# FPGA.net
KiCad netlist of a schematic drawn in Altium Designer
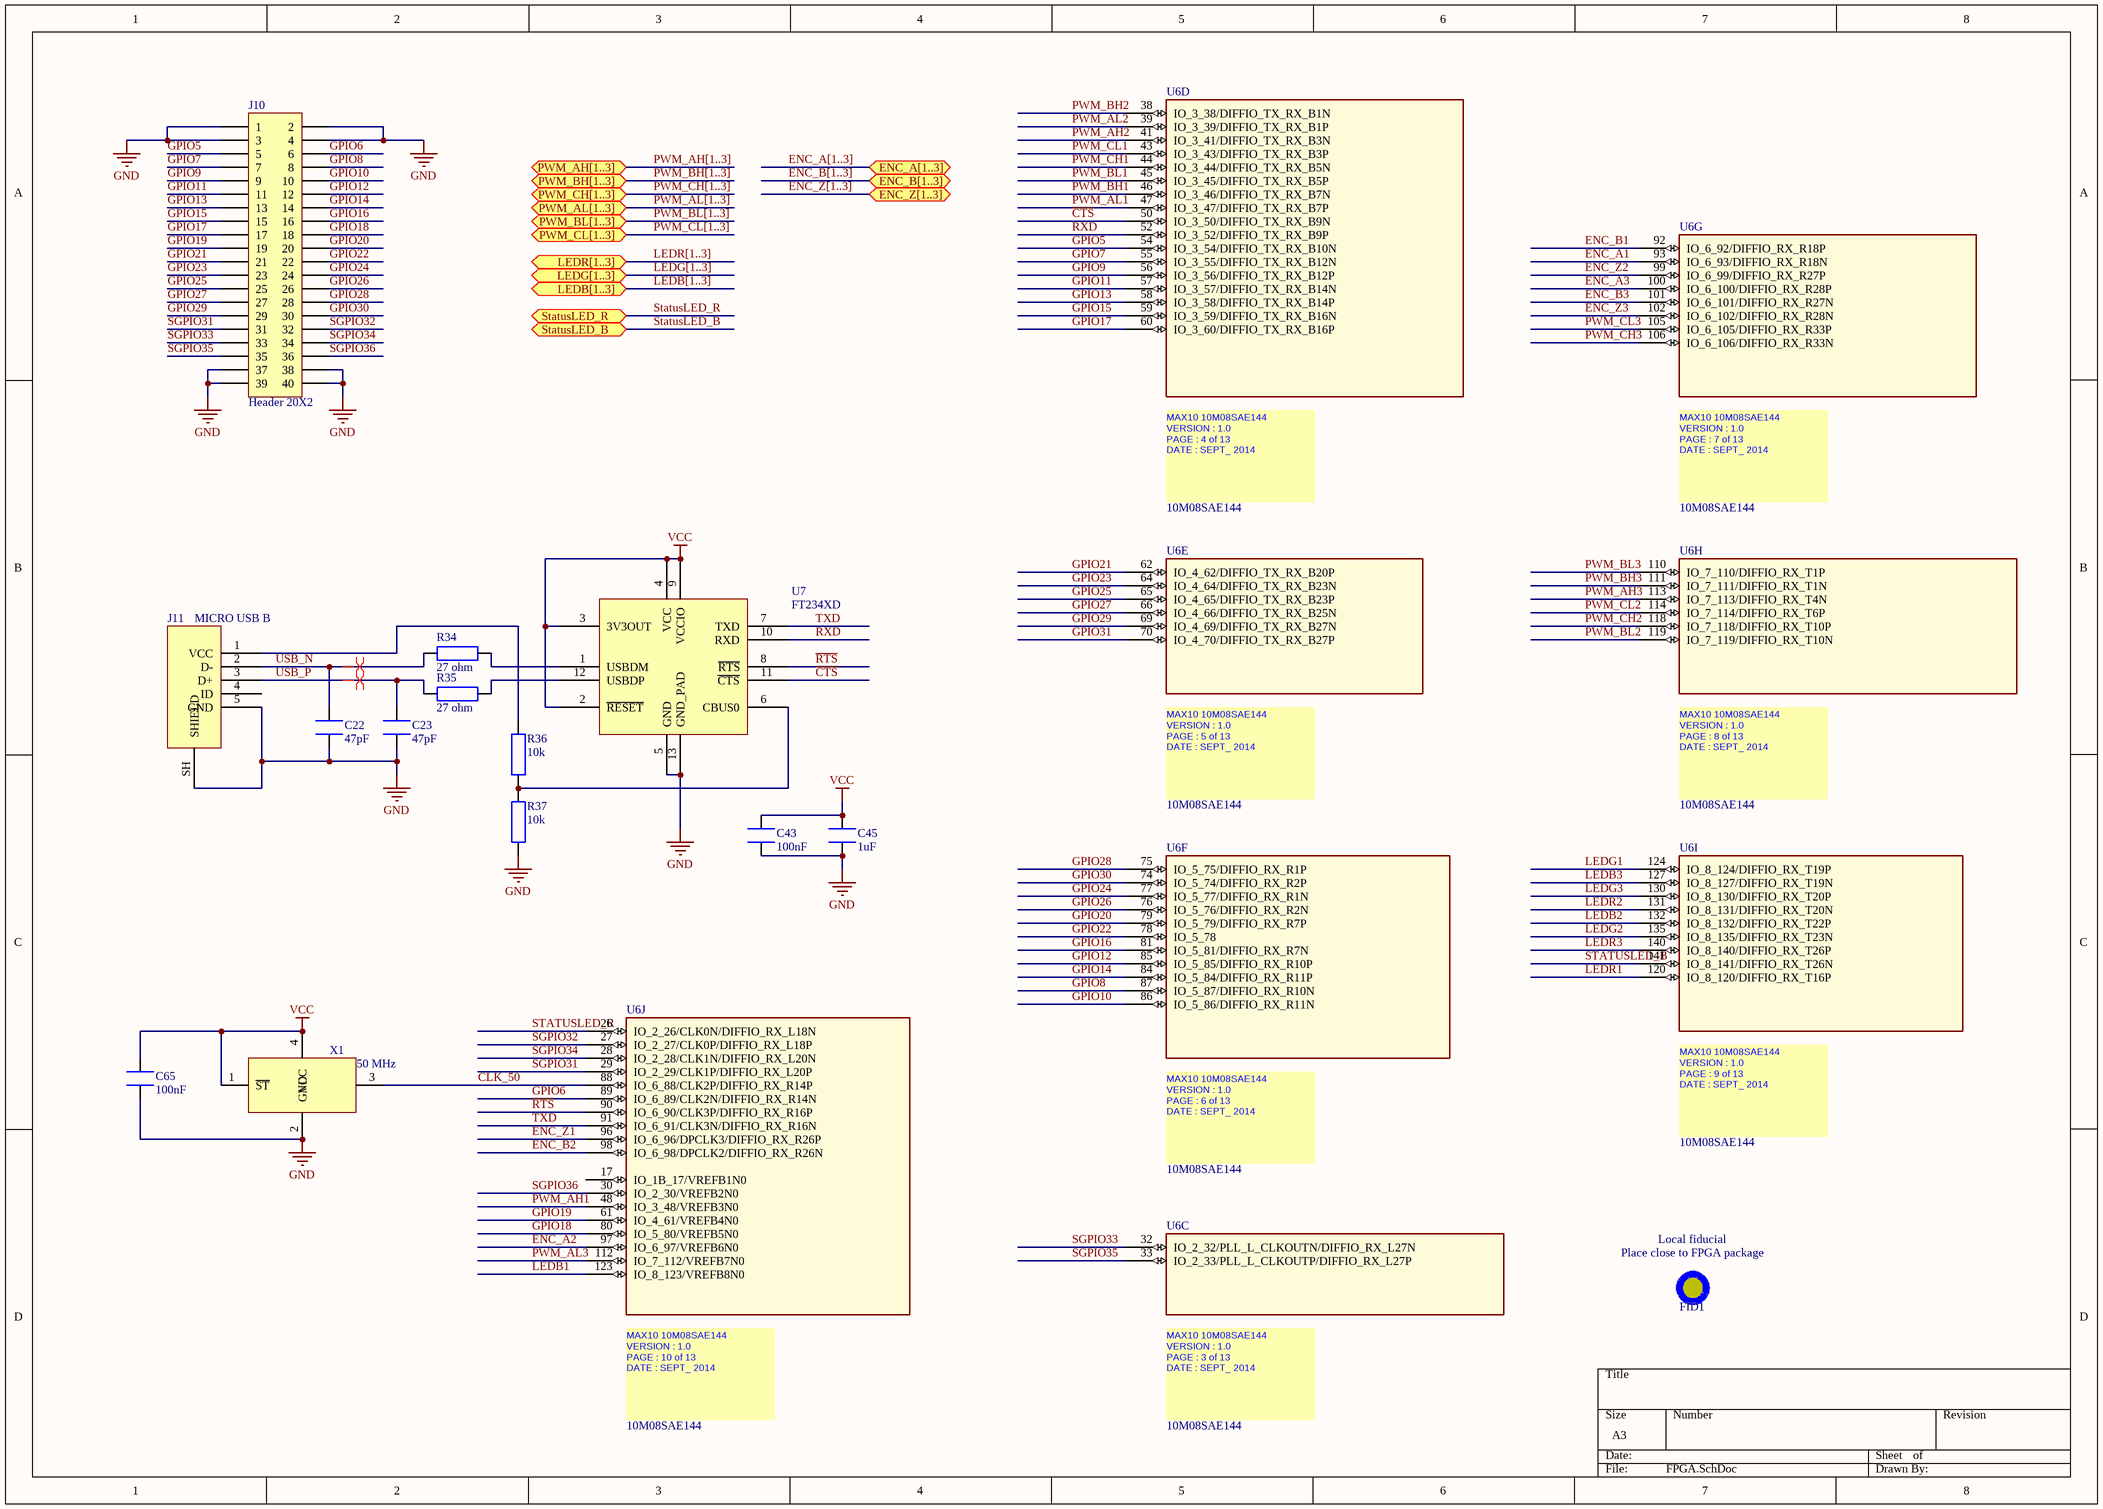
[diagram p0: FPGA.SchDoc]

(export (version "E")
  (design (tool "Eeschema 10.0.6"))
  (components
    (comp (ref "C22")
      (value "47pF")
      (footprint "1608[0603]")
      (description "CAP, MLCC, C0G/NP0, 47PF, 50V, 0603")
      (fields (field (name "Comment") "MC0603N470J500CT"))
      (libsource (lib "CustomComponents") (part "MC0603N470J500CT"))
    )
    (comp (ref "C23")
      (value "47pF")
      (footprint "1608[0603]")
      (description "CAP, MLCC, C0G/NP0, 47PF, 50V, 0603")
      (fields (field (name "Comment") "MC0603N470J500CT"))
      (libsource (lib "CustomComponents") (part "MC0603N470J500CT"))
    )
    (comp (ref "C43")
      (value "100nF")
      (footprint "1608[0603]")
      (description "CAP, MLCC, X7R, 100NF, 16V, 0603")
      (fields (field (name "Comment") "MC0603B104K160CT"))
      (libsource (lib "CustomComponents") (part "MC0603B104K160CT"))
    )
    (comp (ref "C45")
      (value "1uF")
      (footprint "1608[0603]")
      (description "CAP, MLCC, X5R, 1UF, 16V, 0603")
      (fields (field (name "Comment") "MC0603X105K160"))
      (libsource (lib "CustomComponents") (part "MC0603X105K160"))
    )
    (comp (ref "C65")
      (value "100nF")
      (footprint "1608[0603]")
      (description "CAP, MLCC, X7R, 100NF, 16V, 0603")
      (fields (field (name "Comment") "MC0603B104K160CT"))
      (libsource (lib "CustomComponents") (part "MC0603B104K160CT"))
    )
    (comp (ref "FID1")
      (value "FIDUCIAL")
      (footprint "FIDUCIAL")
      (description "1mm Fiducial with 2mm soldermask, 3mm keepout")
      (libsource (lib "CustomComponents") (part "FIDUCIAL"))
    )
    (comp (ref "J10")
      (value "Header 20X2")
      (footprint "HDR2X20")
      (description "Header, 20-Pin, Dual row")
      (fields (field (name "PUBLISHER") "Altium Limited"))
      (libsource (lib "Miscellaneous Connectors") (part "Header 20X2"))
    )
    (comp (ref "J11")
      (value "MICRO USB B")
      (footprint "USB_0103594-0001LF")
      (description "MICRO USB B, RECEPTACLE, SMT, RA, 5WAY")
      (libsource (lib "CustomComponents") (part "10103594-0001LF"))
    )
    (comp (ref "R34")
      (value "27 ohm")
      (footprint "RESC1608X55N")
      (description "RES, THICK FILM, 27OHM, 1%, 0.1W")
      (fields (field (name "Comment") "MCWR06X27R0FTL"))
      (libsource (lib "CustomComponents") (part "MCWR06X27R0FTL"))
    )
    (comp (ref "R35")
      (value "27 ohm")
      (footprint "RESC1608X55N")
      (description "RES, THICK FILM, 27OHM, 1%, 0.1W")
      (fields (field (name "Comment") "MCWR06X27R0FTL"))
      (libsource (lib "CustomComponents") (part "MCWR06X27R0FTL"))
    )
    (comp (ref "R36")
      (value "10k")
      (footprint "RESC1608X06L")
      (description "Resistor, 10k, 0603")
      (fields (field (name "Comment") "MCMR06X1002FTL"))
      (libsource (lib "CustomComponents") (part "MCMR06X1002FTL"))
    )
    (comp (ref "R37")
      (value "10k")
      (footprint "RESC1608X06L")
      (description "Resistor, 10k, 0603")
      (fields (field (name "Comment") "MCMR06X1002FTL"))
      (libsource (lib "CustomComponents") (part "MCMR06X1002FTL"))
    )
    (comp (ref "U6")
      (value "10M08SAE144")
      (footprint "SQFP50P2200X2200X165_HS-145N")
      (libsource (lib "10M08SAREVERSIONTEST_Library") (part "10M08SAE144"))
    )
    (comp (ref "U7")
      (value "FT234XD")
      (footprint "SON45P300X90_HS-13N")
      (libsource (lib "CustomComponents") (part "FT234XD"))
    )
    (comp (ref "X1")
      (value "50 MHz")
      (footprint "SPXO SG-210STF")
      (description "OSCILLATOR, SPXO, SG-210STF, 50 MHZ, SMD")
      (fields (field (name "Comment") "X1G0041710047"))
      (libsource (lib "CustomComponents") (part "X1G0041710047"))
    )
  )
  (nets
    (net (code "1") (name "/CLK_50") (class "Default")
      (node (ref "U6") (pin "88") (pinfunction "IO_6_88/CLK2P/DIFFIO_RX_R14P_88") (pintype "bidirectional"))
      (node (ref "X1") (pin "3") (pinfunction "CLKout_3") (pintype "passive"))
    )
    (net (code "2") (name "/CTS") (class "Default")
      (node (ref "U6") (pin "50") (pinfunction "IO_3_50/DIFFIO_TX_RX_B9N_50") (pintype "bidirectional"))
      (node (ref "U7") (pin "11") (pinfunction "CTS_11") (pintype "passive"))
    )
    (net (code "3") (name "/ENC_A1") (class "Default")
      (node (ref "U6") (pin "93") (pinfunction "IO_6_93/DIFFIO_RX_R18N_93") (pintype "bidirectional"))
    )
    (net (code "4") (name "/ENC_A2") (class "Default")
      (node (ref "U6") (pin "97") (pinfunction "IO_6_97/VREFB6N0_97") (pintype "bidirectional"))
    )
    (net (code "5") (name "/ENC_A3") (class "Default")
      (node (ref "U6") (pin "100") (pinfunction "IO_6_100/DIFFIO_RX_R28P_100") (pintype "bidirectional"))
    )
    (net (code "7") (name "/ENC_B1") (class "Default")
      (node (ref "U6") (pin "92") (pinfunction "IO_6_92/DIFFIO_RX_R18P_92") (pintype "bidirectional"))
    )
    (net (code "8") (name "/ENC_B2") (class "Default")
      (node (ref "U6") (pin "98") (pinfunction "IO_6_98/DPCLK2/DIFFIO_RX_R26N_98") (pintype "bidirectional"))
    )
    (net (code "9") (name "/ENC_B3") (class "Default")
      (node (ref "U6") (pin "101") (pinfunction "IO_6_101/DIFFIO_RX_R27N_101") (pintype "bidirectional"))
    )
    (net (code "11") (name "/ENC_Z1") (class "Default")
      (node (ref "U6") (pin "96") (pinfunction "IO_6_96/DPCLK3/DIFFIO_RX_R26P_96") (pintype "bidirectional"))
    )
    (net (code "12") (name "/ENC_Z2") (class "Default")
      (node (ref "U6") (pin "99") (pinfunction "IO_6_99/DIFFIO_RX_R27P_99") (pintype "bidirectional"))
    )
    (net (code "13") (name "/ENC_Z3") (class "Default")
      (node (ref "U6") (pin "102") (pinfunction "IO_6_102/DIFFIO_RX_R28N_102") (pintype "bidirectional"))
    )
    (net (code "15") (name "/GPIO5") (class "Default")
      (node (ref "J10") (pin "5") (pinfunction "5_5") (pintype "passive"))
      (node (ref "U6") (pin "54") (pinfunction "IO_3_54/DIFFIO_TX_RX_B10N_54") (pintype "bidirectional"))
    )
    (net (code "16") (name "/GPIO6") (class "Default")
      (node (ref "J10") (pin "6") (pinfunction "6_6") (pintype "passive"))
      (node (ref "U6") (pin "89") (pinfunction "IO_6_89/CLK2N/DIFFIO_RX_R14N_89") (pintype "bidirectional"))
    )
    (net (code "17") (name "/GPIO7") (class "Default")
      (node (ref "J10") (pin "7") (pinfunction "7_7") (pintype "passive"))
      (node (ref "U6") (pin "55") (pinfunction "IO_3_55/DIFFIO_TX_RX_B12N_55") (pintype "bidirectional"))
    )
    (net (code "18") (name "/GPIO8") (class "Default")
      (node (ref "J10") (pin "8") (pinfunction "8_8") (pintype "passive"))
      (node (ref "U6") (pin "87") (pinfunction "IO_5_87/DIFFIO_RX_R10N_87") (pintype "bidirectional"))
    )
    (net (code "19") (name "/GPIO9") (class "Default")
      (node (ref "J10") (pin "9") (pinfunction "9_9") (pintype "passive"))
      (node (ref "U6") (pin "56") (pinfunction "IO_3_56/DIFFIO_TX_RX_B12P_56") (pintype "bidirectional"))
    )
    (net (code "20") (name "/GPIO10") (class "Default")
      (node (ref "J10") (pin "10") (pinfunction "10_10") (pintype "passive"))
      (node (ref "U6") (pin "86") (pinfunction "IO_5_86/DIFFIO_RX_R11N_86") (pintype "bidirectional"))
    )
    (net (code "21") (name "/GPIO11") (class "Default")
      (node (ref "J10") (pin "11") (pinfunction "11_11") (pintype "passive"))
      (node (ref "U6") (pin "57") (pinfunction "IO_3_57/DIFFIO_TX_RX_B14N_57") (pintype "bidirectional"))
    )
    (net (code "22") (name "/GPIO12") (class "Default")
      (node (ref "J10") (pin "12") (pinfunction "12_12") (pintype "passive"))
      (node (ref "U6") (pin "85") (pinfunction "IO_5_85/DIFFIO_RX_R10P_85") (pintype "bidirectional"))
    )
    (net (code "23") (name "/GPIO13") (class "Default")
      (node (ref "J10") (pin "13") (pinfunction "13_13") (pintype "passive"))
      (node (ref "U6") (pin "58") (pinfunction "IO_3_58/DIFFIO_TX_RX_B14P_58") (pintype "bidirectional"))
    )
    (net (code "24") (name "/GPIO14") (class "Default")
      (node (ref "J10") (pin "14") (pinfunction "14_14") (pintype "passive"))
      (node (ref "U6") (pin "84") (pinfunction "IO_5_84/DIFFIO_RX_R11P_84") (pintype "bidirectional"))
    )
    (net (code "25") (name "/GPIO15") (class "Default")
      (node (ref "J10") (pin "15") (pinfunction "15_15") (pintype "passive"))
      (node (ref "U6") (pin "59") (pinfunction "IO_3_59/DIFFIO_TX_RX_B16N_59") (pintype "bidirectional"))
    )
    (net (code "26") (name "/GPIO16") (class "Default")
      (node (ref "J10") (pin "16") (pinfunction "16_16") (pintype "passive"))
      (node (ref "U6") (pin "81") (pinfunction "IO_5_81/DIFFIO_RX_R7N_81") (pintype "bidirectional"))
    )
    (net (code "27") (name "/GPIO17") (class "Default")
      (node (ref "J10") (pin "17") (pinfunction "17_17") (pintype "passive"))
      (node (ref "U6") (pin "60") (pinfunction "IO_3_60/DIFFIO_TX_RX_B16P_60") (pintype "bidirectional"))
    )
    (net (code "28") (name "/GPIO18") (class "Default")
      (node (ref "J10") (pin "18") (pinfunction "18_18") (pintype "passive"))
      (node (ref "U6") (pin "80") (pinfunction "IO_5_80/VREFB5N0_80") (pintype "bidirectional"))
    )
    (net (code "29") (name "/GPIO19") (class "Default")
      (node (ref "J10") (pin "19") (pinfunction "19_19") (pintype "passive"))
      (node (ref "U6") (pin "61") (pinfunction "IO_4_61/VREFB4N0_61") (pintype "bidirectional"))
    )
    (net (code "30") (name "/GPIO20") (class "Default")
      (node (ref "J10") (pin "20") (pinfunction "20_20") (pintype "passive"))
      (node (ref "U6") (pin "79") (pinfunction "IO_5_79/DIFFIO_RX_R7P_79") (pintype "bidirectional"))
    )
    (net (code "31") (name "/GPIO21") (class "Default")
      (node (ref "J10") (pin "21") (pinfunction "21_21") (pintype "passive"))
      (node (ref "U6") (pin "62") (pinfunction "IO_4_62/DIFFIO_TX_RX_B20P_62") (pintype "bidirectional"))
    )
    (net (code "32") (name "/GPIO22") (class "Default")
      (node (ref "J10") (pin "22") (pinfunction "22_22") (pintype "passive"))
      (node (ref "U6") (pin "78") (pinfunction "IO_5_78_78") (pintype "bidirectional"))
    )
    (net (code "33") (name "/GPIO23") (class "Default")
      (node (ref "J10") (pin "23") (pinfunction "23_23") (pintype "passive"))
      (node (ref "U6") (pin "64") (pinfunction "IO_4_64/DIFFIO_TX_RX_B23N_64") (pintype "bidirectional"))
    )
    (net (code "34") (name "/GPIO24") (class "Default")
      (node (ref "J10") (pin "24") (pinfunction "24_24") (pintype "passive"))
      (node (ref "U6") (pin "77") (pinfunction "IO_5_77/DIFFIO_RX_R1N_77") (pintype "bidirectional"))
    )
    (net (code "35") (name "/GPIO25") (class "Default")
      (node (ref "J10") (pin "25") (pinfunction "25_25") (pintype "passive"))
      (node (ref "U6") (pin "65") (pinfunction "IO_4_65/DIFFIO_TX_RX_B23P_65") (pintype "bidirectional"))
    )
    (net (code "36") (name "/GPIO26") (class "Default")
      (node (ref "J10") (pin "26") (pinfunction "26_26") (pintype "passive"))
      (node (ref "U6") (pin "76") (pinfunction "IO_5_76/DIFFIO_RX_R2N_76") (pintype "bidirectional"))
    )
    (net (code "37") (name "/GPIO27") (class "Default")
      (node (ref "J10") (pin "27") (pinfunction "27_27") (pintype "passive"))
      (node (ref "U6") (pin "66") (pinfunction "IO_4_66/DIFFIO_TX_RX_B25N_66") (pintype "bidirectional"))
    )
    (net (code "38") (name "/GPIO28") (class "Default")
      (node (ref "J10") (pin "28") (pinfunction "28_28") (pintype "passive"))
      (node (ref "U6") (pin "75") (pinfunction "IO_5_75/DIFFIO_RX_R1P_75") (pintype "bidirectional"))
    )
    (net (code "39") (name "/GPIO29") (class "Default")
      (node (ref "J10") (pin "29") (pinfunction "29_29") (pintype "passive"))
      (node (ref "U6") (pin "69") (pinfunction "IO_4_69/DIFFIO_TX_RX_B27N_69") (pintype "bidirectional"))
    )
    (net (code "40") (name "/GPIO30") (class "Default")
      (node (ref "J10") (pin "30") (pinfunction "30_30") (pintype "passive"))
      (node (ref "U6") (pin "74") (pinfunction "IO_5_74/DIFFIO_RX_R2P_74") (pintype "bidirectional"))
    )
    (net (code "41") (name "/GPIO31") (class "Default")
      (node (ref "U6") (pin "70") (pinfunction "IO_4_70/DIFFIO_TX_RX_B27P_70") (pintype "bidirectional"))
    )
    (net (code "42") (name "/LEDB1") (class "Default")
      (node (ref "U6") (pin "123") (pinfunction "IO_8_123/VREFB8N0_123") (pintype "bidirectional"))
    )
    (net (code "43") (name "/LEDB2") (class "Default")
      (node (ref "U6") (pin "132") (pinfunction "IO_8_132/DIFFIO_RX_T22P_132") (pintype "bidirectional"))
    )
    (net (code "44") (name "/LEDB3") (class "Default")
      (node (ref "U6") (pin "127") (pinfunction "IO_8_127/DIFFIO_RX_T19N_127") (pintype "bidirectional"))
    )
    (net (code "46") (name "/LEDG1") (class "Default")
      (node (ref "U6") (pin "124") (pinfunction "IO_8_124/DIFFIO_RX_T19P_124") (pintype "bidirectional"))
    )
    (net (code "47") (name "/LEDG2") (class "Default")
      (node (ref "U6") (pin "135") (pinfunction "IO_8_135/DIFFIO_RX_T23N_135") (pintype "bidirectional"))
    )
    (net (code "48") (name "/LEDG3") (class "Default")
      (node (ref "U6") (pin "130") (pinfunction "IO_8_130/DIFFIO_RX_T20P_130") (pintype "bidirectional"))
    )
    (net (code "50") (name "/LEDR1") (class "Default")
      (node (ref "U6") (pin "120") (pinfunction "IO_8_120/DIFFIO_RX_T16P_120") (pintype "bidirectional"))
    )
    (net (code "51") (name "/LEDR2") (class "Default")
      (node (ref "U6") (pin "131") (pinfunction "IO_8_131/DIFFIO_RX_T20N_131") (pintype "bidirectional"))
    )
    (net (code "52") (name "/LEDR3") (class "Default")
      (node (ref "U6") (pin "140") (pinfunction "IO_8_140/DIFFIO_RX_T26P_140") (pintype "bidirectional"))
    )
    (net (code "54") (name "/PWM_AH1") (class "Default")
      (node (ref "U6") (pin "48") (pinfunction "IO_3_48/VREFB3N0_48") (pintype "bidirectional"))
    )
    (net (code "55") (name "/PWM_AH2") (class "Default")
      (node (ref "U6") (pin "41") (pinfunction "IO_3_41/DIFFIO_TX_RX_B3N_41") (pintype "bidirectional"))
    )
    (net (code "56") (name "/PWM_AH3") (class "Default")
      (node (ref "U6") (pin "113") (pinfunction "IO_7_113/DIFFIO_RX_T4N_113") (pintype "bidirectional"))
    )
    (net (code "58") (name "/PWM_AL1") (class "Default")
      (node (ref "U6") (pin "47") (pinfunction "IO_3_47/DIFFIO_TX_RX_B7P_47") (pintype "bidirectional"))
    )
    (net (code "59") (name "/PWM_AL2") (class "Default")
      (node (ref "U6") (pin "39") (pinfunction "IO_3_39/DIFFIO_TX_RX_B1P_39") (pintype "bidirectional"))
    )
    (net (code "60") (name "/PWM_AL3") (class "Default")
      (node (ref "U6") (pin "112") (pinfunction "IO_7_112/VREFB7N0_112") (pintype "bidirectional"))
    )
    (net (code "62") (name "/PWM_BH1") (class "Default")
      (node (ref "U6") (pin "46") (pinfunction "IO_3_46/DIFFIO_TX_RX_B7N_46") (pintype "bidirectional"))
    )
    (net (code "63") (name "/PWM_BH2") (class "Default")
      (node (ref "U6") (pin "38") (pinfunction "IO_3_38/DIFFIO_TX_RX_B1N_38") (pintype "bidirectional"))
    )
    (net (code "64") (name "/PWM_BH3") (class "Default")
      (node (ref "U6") (pin "111") (pinfunction "IO_7_111/DIFFIO_RX_T1N_111") (pintype "bidirectional"))
    )
    (net (code "66") (name "/PWM_BL1") (class "Default")
      (node (ref "U6") (pin "45") (pinfunction "IO_3_45/DIFFIO_TX_RX_B5P_45") (pintype "bidirectional"))
    )
    (net (code "67") (name "/PWM_BL2") (class "Default")
      (node (ref "U6") (pin "119") (pinfunction "IO_7_119/DIFFIO_RX_T10N_119") (pintype "bidirectional"))
    )
    (net (code "68") (name "/PWM_BL3") (class "Default")
      (node (ref "U6") (pin "110") (pinfunction "IO_7_110/DIFFIO_RX_T1P_110") (pintype "bidirectional"))
    )
    (net (code "70") (name "/PWM_CH1") (class "Default")
      (node (ref "U6") (pin "44") (pinfunction "IO_3_44/DIFFIO_TX_RX_B5N_44") (pintype "bidirectional"))
    )
    (net (code "71") (name "/PWM_CH2") (class "Default")
      (node (ref "U6") (pin "118") (pinfunction "IO_7_118/DIFFIO_RX_T10P_118") (pintype "bidirectional"))
    )
    (net (code "72") (name "/PWM_CH3") (class "Default")
      (node (ref "U6") (pin "106") (pinfunction "IO_6_106/DIFFIO_RX_R33N_106") (pintype "bidirectional"))
    )
    (net (code "74") (name "/PWM_CL1") (class "Default")
      (node (ref "U6") (pin "43") (pinfunction "IO_3_43/DIFFIO_TX_RX_B3P_43") (pintype "bidirectional"))
    )
    (net (code "75") (name "/PWM_CL2") (class "Default")
      (node (ref "U6") (pin "114") (pinfunction "IO_7_114/DIFFIO_RX_T6P_114") (pintype "bidirectional"))
    )
    (net (code "76") (name "/PWM_CL3") (class "Default")
      (node (ref "U6") (pin "105") (pinfunction "IO_6_105/DIFFIO_RX_R33P_105") (pintype "bidirectional"))
    )
    (net (code "78") (name "/RTS") (class "Default")
      (node (ref "U6") (pin "90") (pinfunction "IO_6_90/CLK3P/DIFFIO_RX_R16P_90") (pintype "bidirectional"))
      (node (ref "U7") (pin "8") (pinfunction "RTS_8") (pintype "passive"))
    )
    (net (code "79") (name "/RXD") (class "Default")
      (node (ref "U6") (pin "52") (pinfunction "IO_3_52/DIFFIO_TX_RX_B9P_52") (pintype "bidirectional"))
      (node (ref "U7") (pin "10") (pinfunction "RXD_10") (pintype "passive"))
    )
    (net (code "80") (name "/SGPIO31") (class "Default")
      (node (ref "J10") (pin "31") (pinfunction "31_31") (pintype "passive"))
      (node (ref "U6") (pin "29") (pinfunction "IO_2_29/CLK1P/DIFFIO_RX_L20P_29") (pintype "bidirectional"))
    )
    (net (code "81") (name "/SGPIO32") (class "Default")
      (node (ref "J10") (pin "32") (pinfunction "32_32") (pintype "passive"))
      (node (ref "U6") (pin "27") (pinfunction "IO_2_27/CLK0P/DIFFIO_RX_L18P_27") (pintype "bidirectional"))
    )
    (net (code "82") (name "/SGPIO33") (class "Default")
      (node (ref "J10") (pin "33") (pinfunction "33_33") (pintype "passive"))
      (node (ref "U6") (pin "32") (pinfunction "IO_2_32/PLL_L_CLKOUTN/DIFFIO_RX_L27N_32") (pintype "bidirectional"))
    )
    (net (code "83") (name "/SGPIO34") (class "Default")
      (node (ref "J10") (pin "34") (pinfunction "34_34") (pintype "passive"))
      (node (ref "U6") (pin "28") (pinfunction "IO_2_28/CLK1N/DIFFIO_RX_L20N_28") (pintype "bidirectional"))
    )
    (net (code "84") (name "/SGPIO35") (class "Default")
      (node (ref "J10") (pin "35") (pinfunction "35_35") (pintype "passive"))
      (node (ref "U6") (pin "33") (pinfunction "IO_2_33/PLL_L_CLKOUTP/DIFFIO_RX_L27P_33") (pintype "bidirectional"))
    )
    (net (code "85") (name "/SGPIO36") (class "Default")
      (node (ref "J10") (pin "36") (pinfunction "36_36") (pintype "passive"))
      (node (ref "U6") (pin "30") (pinfunction "IO_2_30/VREFB2N0_30") (pintype "bidirectional"))
    )
    (net (code "86") (name "/STATUSLED_B") (class "Default")
      (node (ref "U6") (pin "141") (pinfunction "IO_8_141/DIFFIO_RX_T26N_141") (pintype "bidirectional"))
    )
    (net (code "87") (name "/STATUSLED_R") (class "Default")
      (node (ref "U6") (pin "26") (pinfunction "IO_2_26/CLK0N/DIFFIO_RX_L18N_26") (pintype "bidirectional"))
    )
    (net (code "90") (name "/TXD") (class "Default")
      (node (ref "U6") (pin "91") (pinfunction "IO_6_91/CLK3N/DIFFIO_RX_R16N_91") (pintype "bidirectional"))
      (node (ref "U7") (pin "7") (pinfunction "TXD_7") (pintype "passive"))
    )
    (net (code "91") (name "/USB_N") (class "Default")
      (node (ref "C22") (pin "2") (pinfunction "2_2") (pintype "passive"))
      (node (ref "J11") (pin "2") (pinfunction "D-_2") (pintype "passive"))
      (node (ref "R34") (pin "2") (pinfunction "0_2") (pintype "passive"))
    )
    (net (code "92") (name "/USB_P") (class "Default")
      (node (ref "C23") (pin "2") (pinfunction "2_2") (pintype "passive"))
      (node (ref "J11") (pin "3") (pinfunction "D+_3") (pintype "passive"))
      (node (ref "R35") (pin "2") (pinfunction "0_2") (pintype "passive"))
    )
    (net (code "93") (name "GND") (class "Default")
      (node (ref "C22") (pin "1") (pinfunction "1_1") (pintype "passive"))
      (node (ref "C23") (pin "1") (pinfunction "1_1") (pintype "passive"))
      (node (ref "C43") (pin "1") (pinfunction "1_1") (pintype "passive"))
      (node (ref "C45") (pin "1") (pinfunction "1_1") (pintype "passive"))
      (node (ref "C65") (pin "1") (pinfunction "1_1") (pintype "passive"))
      (node (ref "J10") (pin "1") (pinfunction "1_1") (pintype "passive"))
      (node (ref "J10") (pin "2") (pinfunction "2_2") (pintype "passive"))
      (node (ref "J10") (pin "3") (pinfunction "3_3") (pintype "passive"))
      (node (ref "J10") (pin "37") (pinfunction "37_37") (pintype "passive"))
      (node (ref "J10") (pin "38") (pinfunction "38_38") (pintype "passive"))
      (node (ref "J10") (pin "39") (pinfunction "39_39") (pintype "passive"))
      (node (ref "J10") (pin "4") (pinfunction "4_4") (pintype "passive"))
      (node (ref "J10") (pin "40") (pinfunction "40_40") (pintype "passive"))
      (node (ref "J11") (pin "5") (pinfunction "GND_5") (pintype "passive"))
      (node (ref "J11") (pin "SH") (pinfunction "SHIELD_SH") (pintype "passive"))
      (node (ref "R37") (pin "1") (pinfunction "0_1") (pintype "passive"))
      (node (ref "U7") (pin "13") (pinfunction "GND_PAD_13") (pintype "passive"))
      (node (ref "U7") (pin "5") (pinfunction "GND_5") (pintype "passive"))
      (node (ref "X1") (pin "2") (pinfunction "GND_2") (pintype "passive"))
    )
    (net (code "94") (name "Net-(J11-VCC)") (class "Default")
      (node (ref "J11") (pin "1") (pinfunction "VCC_1") (pintype "passive"))
      (node (ref "R36") (pin "2") (pinfunction "0_2") (pintype "passive"))
    )
    (net (code "95") (name "Net-(U7-CBUS0)") (class "Default")
      (node (ref "R36") (pin "1") (pinfunction "0_1") (pintype "passive"))
      (node (ref "R37") (pin "2") (pinfunction "0_2") (pintype "passive"))
      (node (ref "U7") (pin "6") (pinfunction "CBUS0_6") (pintype "passive"))
    )
    (net (code "96") (name "Net-(U7-USBDM)") (class "Default")
      (node (ref "R34") (pin "1") (pinfunction "0_1") (pintype "passive"))
      (node (ref "U7") (pin "1") (pinfunction "USBDM_1") (pintype "passive"))
    )
    (net (code "97") (name "Net-(U7-USBDP)") (class "Default")
      (node (ref "R35") (pin "1") (pinfunction "0_1") (pintype "passive"))
      (node (ref "U7") (pin "12") (pinfunction "USBDP_12") (pintype "passive"))
    )
    (net (code "98") (name "VCC") (class "Default")
      (node (ref "C43") (pin "2") (pinfunction "2_2") (pintype "passive"))
      (node (ref "C45") (pin "2") (pinfunction "2_2") (pintype "passive"))
      (node (ref "C65") (pin "2") (pinfunction "2_2") (pintype "passive"))
      (node (ref "U7") (pin "2") (pinfunction "RESET_2") (pintype "passive"))
      (node (ref "U7") (pin "3") (pinfunction "3V3OUT_3") (pintype "passive"))
      (node (ref "U7") (pin "4") (pinfunction "VCC_4") (pintype "passive"))
      (node (ref "U7") (pin "9") (pinfunction "VCCIO_9") (pintype "passive"))
      (node (ref "X1") (pin "1") (pinfunction "~{ST}_1") (pintype "passive"))
      (node (ref "X1") (pin "4") (pinfunction "VCC_4") (pintype "passive"))
    )
    (net (code "99") (name "unconnected-(J11-ID-Pad4)") (class "Default")
      (node (ref "J11") (pin "4") (pinfunction "ID_4") (pintype "passive"))
    )
    (net (code "100") (name "unconnected-(U6J-IO_1B_17{slash}VREFB1N0-Pad17)") (class "Default")
      (node (ref "U6") (pin "17") (pinfunction "IO_1B_17/VREFB1N0_17") (pintype "bidirectional"))
    )
  )
)
